# Atmega.net
KiCad netlist of a schematic drawn in EAGLE
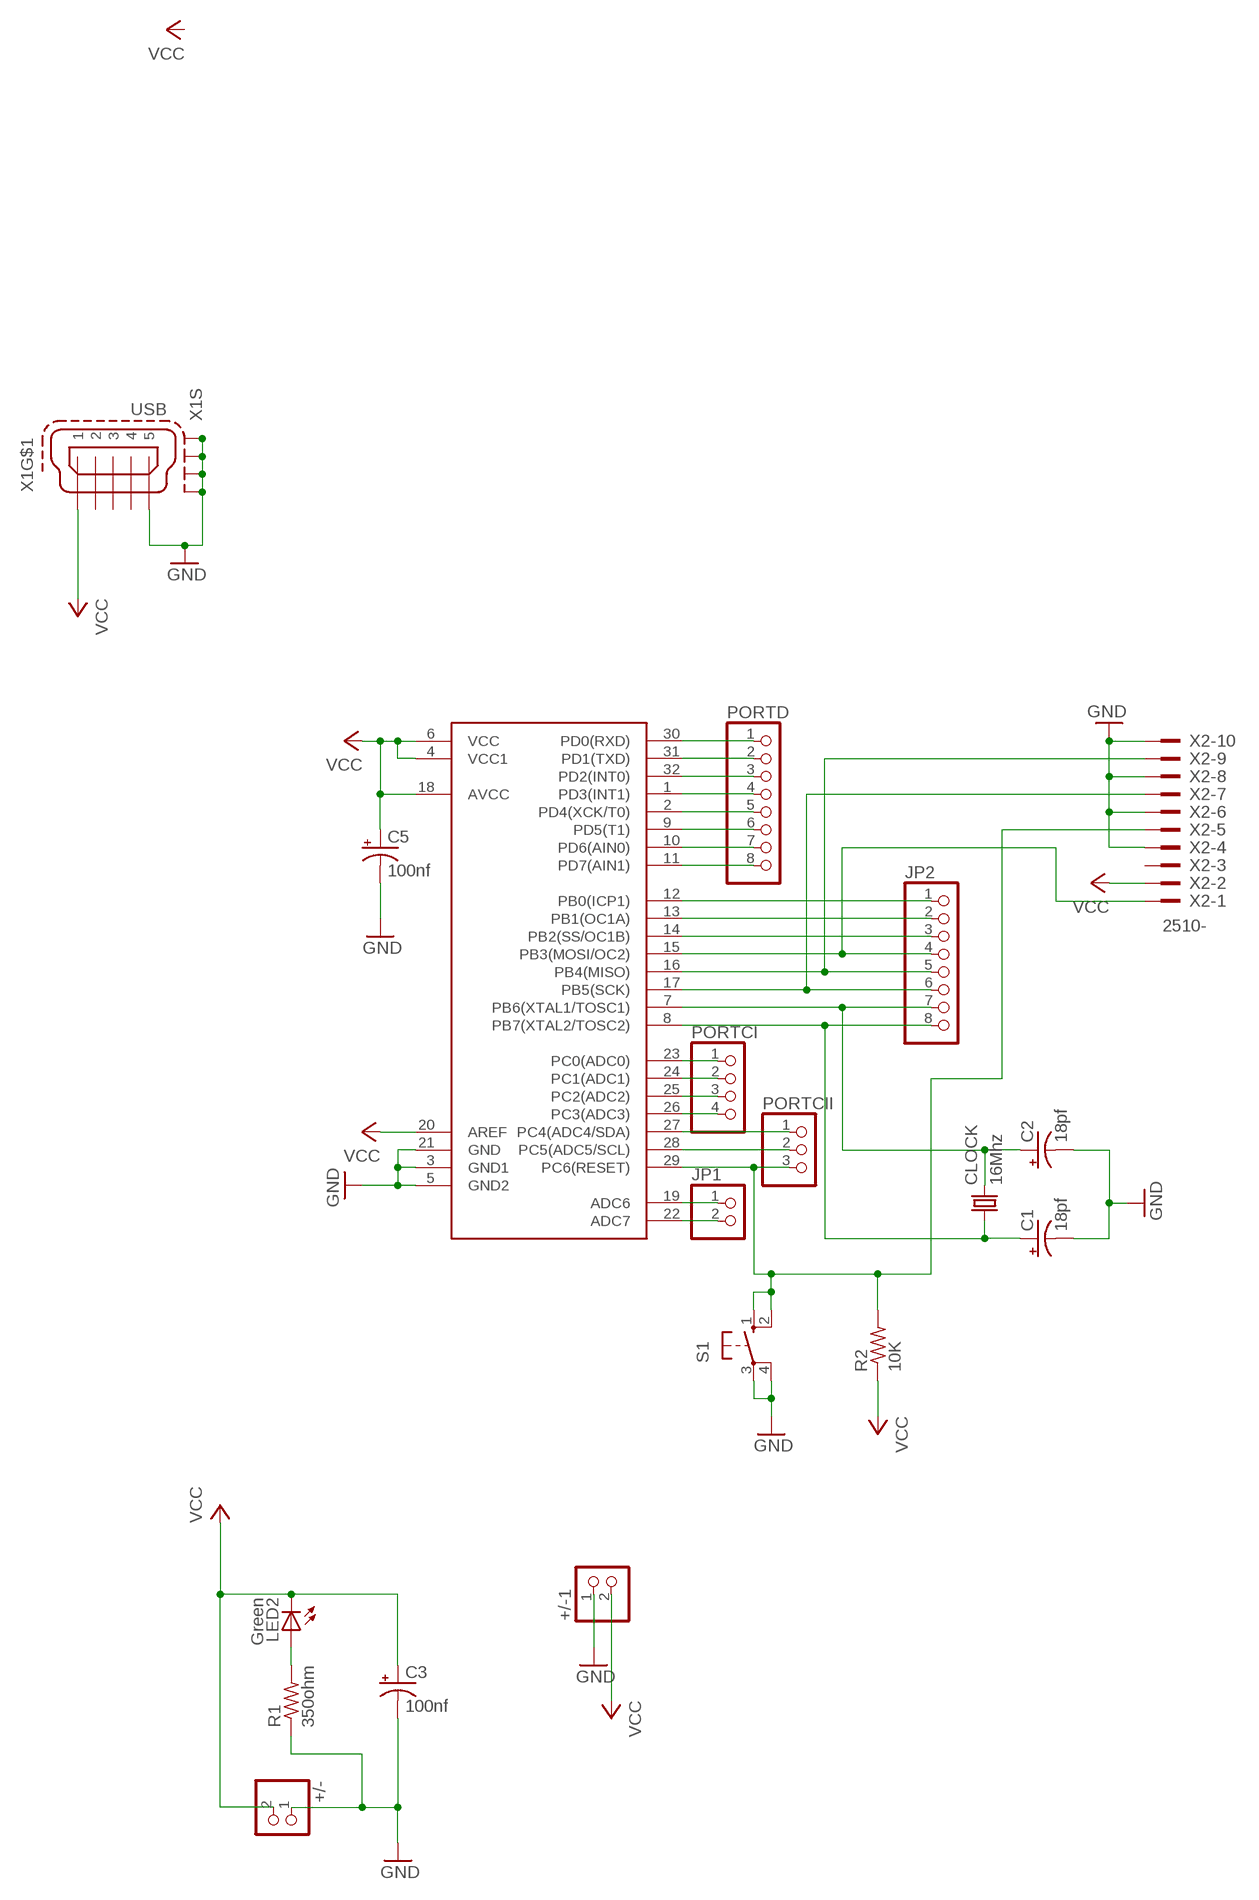
[diagram p0: schematic, sheet 1]

(export (version "E")
  (design (tool "Eeschema 10.0.6"))
  (components
    (comp (ref "+/-")
      (value "PINHD-1X2")
      (footprint "eagle-import:1X02")
      (libsource (lib "eagle-import") (part "PINHD-1X2"))
    )
    (comp (ref "+/-1")
      (value "PINHD-1X2")
      (footprint "eagle-import:1X02")
      (libsource (lib "eagle-import") (part "PINHD-1X2"))
    )
    (comp (ref "C1")
      (value "18pf")
      (footprint "eagle-import:SMC_Z")
      (libsource (lib "eagle-import") (part "CPOL-USSMCZ"))
    )
    (comp (ref "C2")
      (value "18pf")
      (footprint "eagle-import:SMC_Z")
      (libsource (lib "eagle-import") (part "CPOL-USSMCZ"))
    )
    (comp (ref "C3")
      (value "100nf")
      (footprint "eagle-import:SMC_Z")
      (libsource (lib "eagle-import") (part "CPOL-USSMCZ"))
    )
    (comp (ref "C5")
      (value "100nf")
      (footprint "eagle-import:SMC_Z")
      (libsource (lib "eagle-import") (part "CPOL-USSMCZ"))
    )
    (comp (ref "CLOCK")
      (value "16Mhz")
      (footprint "eagle-import:HC49UP")
      (libsource (lib "eagle-import") (part "CRYSTALHC49UP"))
    )
    (comp (ref "JP1")
      (value "PINHD-1X2")
      (footprint "eagle-import:1X02")
      (libsource (lib "eagle-import") (part "PINHD-1X2"))
    )
    (comp (ref "JP2")
      (value "PINHD-1X8")
      (footprint "eagle-import:1X08")
      (libsource (lib "eagle-import") (part "PINHD-1X8"))
    )
    (comp (ref "LED2")
      (value "Green")
      (footprint "eagle-import:PLCC2")
      (fields (field (name "COLOR") "green"))
      (libsource (lib "eagle-import") (part "_T679-?-1E1F1LG"))
    )
    (comp (ref "PORTCI")
      (value "PINHD-1X4")
      (footprint "eagle-import:1X04")
      (libsource (lib "eagle-import") (part "PINHD-1X4"))
    )
    (comp (ref "PORTCII")
      (value "PINHD-1X3")
      (footprint "eagle-import:1X03")
      (libsource (lib "eagle-import") (part "PINHD-1X3"))
    )
    (comp (ref "PORTD")
      (value "PINHD-1X8")
      (footprint "eagle-import:1X08")
      (libsource (lib "eagle-import") (part "PINHD-1X8"))
    )
    (comp (ref "R1")
      (value "350ohm")
      (footprint "eagle-import:M0805")
      (libsource (lib "eagle-import") (part "R-US_M0805"))
    )
    (comp (ref "R2")
      (value "10K")
      (footprint "eagle-import:M0805")
      (libsource (lib "eagle-import") (part "R-US_M0805"))
    )
    (comp (ref "S1")
      (value "10-XX")
      (footprint "eagle-import:B3F-10XX")
      (fields (field (name "MPN") "B3F-1000"))
      (libsource (lib "eagle-import") (part "10-XX"))
    )
    (comp (ref "U$1")
      (value "ATMEGA8A")
      (footprint "eagle-import:TQFP32-08")
      (libsource (lib "eagle-import") (part "ATMEGA8A"))
    )
    (comp (ref "X1")
      (value "USB")
      (footprint "eagle-import:32005-201")
      (libsource (lib "eagle-import") (part "MINI-USB-SCHIELD-32005-201"))
    )
    (comp (ref "X2")
      (value "2510-")
      (footprint "eagle-import:PAK100_2500-10")
      (fields (field (name "MF") "3M") (field (name "MPN") "2510-6002UB"))
      (libsource (lib "eagle-import") (part "2510-"))
    )
  )
  (nets
    (net (code "1") (name "GND") (class "Default")
      (node (ref "+/-") (pin "1") (pinfunction "1_1") (pintype "passive"))
      (node (ref "+/-1") (pin "1") (pinfunction "1_1") (pintype "passive"))
      (node (ref "C1") (pin "-") (pinfunction "-_-") (pintype "passive"))
      (node (ref "C2") (pin "-") (pinfunction "-_-") (pintype "passive"))
      (node (ref "C3") (pin "-") (pinfunction "-_-") (pintype "passive"))
      (node (ref "C5") (pin "-") (pinfunction "-_-") (pintype "passive"))
      (node (ref "R1") (pin "1") (pinfunction "1_1") (pintype "passive"))
      (node (ref "S1") (pin "3") (pinfunction "P_3") (pintype "passive"))
      (node (ref "S1") (pin "4") (pinfunction "P1_4") (pintype "passive"))
      (node (ref "U$1") (pin "21") (pinfunction "GND_21") (pintype "bidirectional"))
      (node (ref "U$1") (pin "3") (pinfunction "GND1_3") (pintype "bidirectional"))
      (node (ref "U$1") (pin "5") (pinfunction "GND2_5") (pintype "bidirectional"))
      (node (ref "X1") (pin "5") (pinfunction "5_5") (pintype "passive"))
      (node (ref "X1") (pin "M1") (pinfunction "S1_M1") (pintype "passive"))
      (node (ref "X1") (pin "M2") (pinfunction "S2_M2") (pintype "passive"))
      (node (ref "X1") (pin "M3") (pinfunction "S3_M3") (pintype "passive"))
      (node (ref "X1") (pin "M4") (pinfunction "S4_M4") (pintype "passive"))
      (node (ref "X2") (pin "10") (pinfunction "KL_10") (pintype "passive"))
      (node (ref "X2") (pin "4") (pinfunction "KL_4") (pintype "passive"))
      (node (ref "X2") (pin "6") (pinfunction "KL_6") (pintype "passive"))
      (node (ref "X2") (pin "8") (pinfunction "KL_8") (pintype "passive"))
    )
    (net (code "2") (name "Net-(LED2-PadA)") (class "Default")
      (node (ref "LED2") (pin "A") (pinfunction "A_A") (pintype "passive"))
      (node (ref "R1") (pin "2") (pinfunction "2_2") (pintype "passive"))
    )
    (net (code "3") (name "Net-(S1-S)") (class "Default")
      (node (ref "PORTCII") (pin "3") (pinfunction "3_3") (pintype "passive"))
      (node (ref "R2") (pin "2") (pinfunction "2_2") (pintype "passive"))
      (node (ref "S1") (pin "1") (pinfunction "S_1") (pintype "passive"))
      (node (ref "S1") (pin "2") (pinfunction "S1_2") (pintype "passive"))
      (node (ref "U$1") (pin "29") (pinfunction "PC6(RESET)_29") (pintype "bidirectional"))
      (node (ref "X2") (pin "5") (pinfunction "KL_5") (pintype "passive"))
    )
    (net (code "4") (name "Net-(U$1-ADC6)") (class "Default")
      (node (ref "JP1") (pin "1") (pinfunction "1_1") (pintype "passive"))
      (node (ref "U$1") (pin "19") (pinfunction "ADC6_19") (pintype "bidirectional"))
    )
    (net (code "5") (name "Net-(U$1-ADC7)") (class "Default")
      (node (ref "JP1") (pin "2") (pinfunction "2_2") (pintype "passive"))
      (node (ref "U$1") (pin "22") (pinfunction "ADC7_22") (pintype "bidirectional"))
    )
    (net (code "6") (name "Net-(U$1-PB0(ICP1))") (class "Default")
      (node (ref "JP2") (pin "1") (pinfunction "1_1") (pintype "passive"))
      (node (ref "U$1") (pin "12") (pinfunction "PB0(ICP1)_12") (pintype "bidirectional"))
    )
    (net (code "7") (name "Net-(U$1-PB1(OC1A))") (class "Default")
      (node (ref "JP2") (pin "2") (pinfunction "2_2") (pintype "passive"))
      (node (ref "U$1") (pin "13") (pinfunction "PB1(OC1A)_13") (pintype "bidirectional"))
    )
    (net (code "8") (name "Net-(U$1-PB2(SS{slash}OC1B))") (class "Default")
      (node (ref "JP2") (pin "3") (pinfunction "3_3") (pintype "passive"))
      (node (ref "U$1") (pin "14") (pinfunction "PB2(SS/OC1B)_14") (pintype "bidirectional"))
    )
    (net (code "9") (name "Net-(U$1-PB3(MOSI{slash}OC2))") (class "Default")
      (node (ref "JP2") (pin "4") (pinfunction "4_4") (pintype "passive"))
      (node (ref "U$1") (pin "15") (pinfunction "PB3(MOSI/OC2)_15") (pintype "bidirectional"))
      (node (ref "X2") (pin "1") (pinfunction "KL_1") (pintype "passive"))
    )
    (net (code "10") (name "Net-(U$1-PB4(MISO))") (class "Default")
      (node (ref "JP2") (pin "5") (pinfunction "5_5") (pintype "passive"))
      (node (ref "U$1") (pin "16") (pinfunction "PB4(MISO)_16") (pintype "bidirectional"))
      (node (ref "X2") (pin "9") (pinfunction "KL_9") (pintype "passive"))
    )
    (net (code "11") (name "Net-(U$1-PB5(SCK))") (class "Default")
      (node (ref "JP2") (pin "6") (pinfunction "6_6") (pintype "passive"))
      (node (ref "U$1") (pin "17") (pinfunction "PB5(SCK)_17") (pintype "bidirectional"))
      (node (ref "X2") (pin "7") (pinfunction "KL_7") (pintype "passive"))
    )
    (net (code "12") (name "Net-(U$1-PB6(XTAL1{slash}TOSC1))") (class "Default")
      (node (ref "C2") (pin "+") (pinfunction "+_+") (pintype "passive"))
      (node (ref "CLOCK") (pin "2") (pinfunction "2_2") (pintype "passive"))
      (node (ref "JP2") (pin "7") (pinfunction "7_7") (pintype "passive"))
      (node (ref "U$1") (pin "7") (pinfunction "PB6(XTAL1/TOSC1)_7") (pintype "bidirectional"))
    )
    (net (code "13") (name "Net-(U$1-PB7(XTAL2{slash}TOSC2))") (class "Default")
      (node (ref "C1") (pin "+") (pinfunction "+_+") (pintype "passive"))
      (node (ref "CLOCK") (pin "1") (pinfunction "1_1") (pintype "passive"))
      (node (ref "JP2") (pin "8") (pinfunction "8_8") (pintype "passive"))
      (node (ref "U$1") (pin "8") (pinfunction "PB7(XTAL2/TOSC2)_8") (pintype "bidirectional"))
    )
    (net (code "14") (name "Net-(U$1-PC0(ADC0))") (class "Default")
      (node (ref "PORTCI") (pin "1") (pinfunction "1_1") (pintype "passive"))
      (node (ref "U$1") (pin "23") (pinfunction "PC0(ADC0)_23") (pintype "bidirectional"))
    )
    (net (code "15") (name "Net-(U$1-PC1(ADC1))") (class "Default")
      (node (ref "PORTCI") (pin "2") (pinfunction "2_2") (pintype "passive"))
      (node (ref "U$1") (pin "24") (pinfunction "PC1(ADC1)_24") (pintype "bidirectional"))
    )
    (net (code "16") (name "Net-(U$1-PC2(ADC2))") (class "Default")
      (node (ref "PORTCI") (pin "3") (pinfunction "3_3") (pintype "passive"))
      (node (ref "U$1") (pin "25") (pinfunction "PC2(ADC2)_25") (pintype "bidirectional"))
    )
    (net (code "17") (name "Net-(U$1-PC3(ADC3))") (class "Default")
      (node (ref "PORTCI") (pin "4") (pinfunction "4_4") (pintype "passive"))
      (node (ref "U$1") (pin "26") (pinfunction "PC3(ADC3)_26") (pintype "bidirectional"))
    )
    (net (code "18") (name "Net-(U$1-PC4(ADC4{slash}SDA))") (class "Default")
      (node (ref "PORTCII") (pin "1") (pinfunction "1_1") (pintype "passive"))
      (node (ref "U$1") (pin "27") (pinfunction "PC4(ADC4/SDA)_27") (pintype "bidirectional"))
    )
    (net (code "19") (name "Net-(U$1-PC5(ADC5{slash}SCL))") (class "Default")
      (node (ref "PORTCII") (pin "2") (pinfunction "2_2") (pintype "passive"))
      (node (ref "U$1") (pin "28") (pinfunction "PC5(ADC5/SCL)_28") (pintype "bidirectional"))
    )
    (net (code "20") (name "Net-(U$1-PD0(RXD))") (class "Default")
      (node (ref "PORTD") (pin "1") (pinfunction "1_1") (pintype "passive"))
      (node (ref "U$1") (pin "30") (pinfunction "PD0(RXD)_30") (pintype "bidirectional"))
    )
    (net (code "21") (name "Net-(U$1-PD1(TXD))") (class "Default")
      (node (ref "PORTD") (pin "2") (pinfunction "2_2") (pintype "passive"))
      (node (ref "U$1") (pin "31") (pinfunction "PD1(TXD)_31") (pintype "bidirectional"))
    )
    (net (code "22") (name "Net-(U$1-PD2(INT0))") (class "Default")
      (node (ref "PORTD") (pin "3") (pinfunction "3_3") (pintype "passive"))
      (node (ref "U$1") (pin "32") (pinfunction "PD2(INT0)_32") (pintype "bidirectional"))
    )
    (net (code "23") (name "Net-(U$1-PD3(INT1))") (class "Default")
      (node (ref "PORTD") (pin "4") (pinfunction "4_4") (pintype "passive"))
      (node (ref "U$1") (pin "1") (pinfunction "PD3(INT1)_1") (pintype "bidirectional"))
    )
    (net (code "24") (name "Net-(U$1-PD4(XCK{slash}T0))") (class "Default")
      (node (ref "PORTD") (pin "5") (pinfunction "5_5") (pintype "passive"))
      (node (ref "U$1") (pin "2") (pinfunction "PD4(XCK/T0)_2") (pintype "bidirectional"))
    )
    (net (code "25") (name "Net-(U$1-PD5(T1))") (class "Default")
      (node (ref "PORTD") (pin "6") (pinfunction "6_6") (pintype "passive"))
      (node (ref "U$1") (pin "9") (pinfunction "PD5(T1)_9") (pintype "bidirectional"))
    )
    (net (code "26") (name "Net-(U$1-PD6(AIN0))") (class "Default")
      (node (ref "PORTD") (pin "7") (pinfunction "7_7") (pintype "passive"))
      (node (ref "U$1") (pin "10") (pinfunction "PD6(AIN0)_10") (pintype "bidirectional"))
    )
    (net (code "27") (name "Net-(U$1-PD7(AIN1))") (class "Default")
      (node (ref "PORTD") (pin "8") (pinfunction "8_8") (pintype "passive"))
      (node (ref "U$1") (pin "11") (pinfunction "PD7(AIN1)_11") (pintype "bidirectional"))
    )
    (net (code "28") (name "VCC") (class "Default")
      (node (ref "+/-") (pin "2") (pinfunction "2_2") (pintype "passive"))
      (node (ref "+/-1") (pin "2") (pinfunction "2_2") (pintype "passive"))
      (node (ref "C3") (pin "+") (pinfunction "+_+") (pintype "passive"))
      (node (ref "C5") (pin "+") (pinfunction "+_+") (pintype "passive"))
      (node (ref "LED2") (pin "C") (pinfunction "C_C") (pintype "passive"))
      (node (ref "R2") (pin "1") (pinfunction "1_1") (pintype "passive"))
      (node (ref "U$1") (pin "18") (pinfunction "AVCC_18") (pintype "bidirectional"))
      (node (ref "U$1") (pin "20") (pinfunction "AREF_20") (pintype "bidirectional"))
      (node (ref "U$1") (pin "4") (pinfunction "VCC1_4") (pintype "bidirectional"))
      (node (ref "U$1") (pin "6") (pinfunction "VCC_6") (pintype "bidirectional"))
      (node (ref "X1") (pin "1") (pinfunction "1_1") (pintype "passive"))
      (node (ref "X2") (pin "2") (pinfunction "KL_2") (pintype "passive"))
    )
    (net (code "29") (name "unconnected-(X1-Pad2)") (class "Default")
      (node (ref "X1") (pin "2") (pinfunction "2_2") (pintype "passive"))
    )
    (net (code "30") (name "unconnected-(X1-Pad3)") (class "Default")
      (node (ref "X1") (pin "3") (pinfunction "3_3") (pintype "passive"))
    )
    (net (code "31") (name "unconnected-(X1-Pad4)") (class "Default")
      (node (ref "X1") (pin "4") (pinfunction "4_4") (pintype "passive"))
    )
    (net (code "32") (name "unconnected-(X2D-KL-Pad3)") (class "Default")
      (node (ref "X2") (pin "3") (pinfunction "KL_3") (pintype "passive"))
    )
  )
)
